# design.net
KiCad netlist of a schematic drawn in Altium Designer
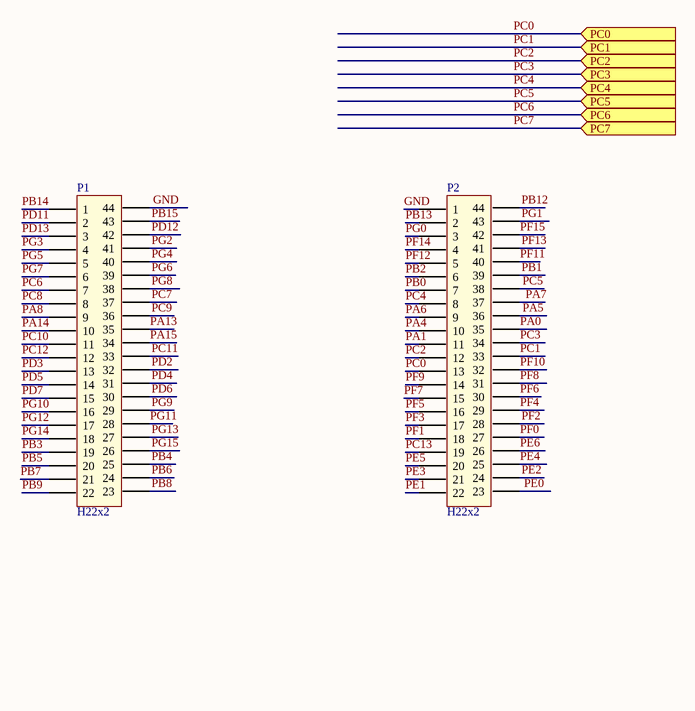
[diagram p0: 接口.SchDoc]

(export (version "E")
  (design (tool "Eeschema 10.0.6"))
  (components
    (comp (ref "P1") (value "H22x2") (footprint "HDR2.54-F-44P") (libsource (lib "Sean") (part "H22x2")))
    (comp (ref "P2") (value "H22x2") (footprint "HDR2.54-F-44P") (libsource (lib "Sean") (part "H22x2")))
  )
  (nets
    (net (code "1") (name "/GND") (class "Default")
      (node (ref "P1") (pin "44") (pinfunction "44_44") (pintype "passive"))
      (node (ref "P2") (pin "1") (pinfunction "1_1") (pintype "passive"))
    )
    (net (code "2") (name "/PA0") (class "Default")
      (node (ref "P2") (pin "35") (pinfunction "35_35") (pintype "passive"))
    )
    (net (code "3") (name "/PA1") (class "Default")
      (node (ref "P2") (pin "11") (pinfunction "11_11") (pintype "passive"))
    )
    (net (code "4") (name "/PA4") (class "Default")
      (node (ref "P2") (pin "10") (pinfunction "10_10") (pintype "passive"))
    )
    (net (code "5") (name "/PA5") (class "Default")
      (node (ref "P2") (pin "36") (pinfunction "36_36") (pintype "passive"))
    )
    (net (code "6") (name "/PA6") (class "Default")
      (node (ref "P2") (pin "9") (pinfunction "9_9") (pintype "passive"))
    )
    (net (code "7") (name "/PA7") (class "Default")
      (node (ref "P2") (pin "37") (pinfunction "37_37") (pintype "passive"))
    )
    (net (code "8") (name "/PA8") (class "Default")
      (node (ref "P1") (pin "9") (pinfunction "9_9") (pintype "passive"))
    )
    (net (code "9") (name "/PA13") (class "Default")
      (node (ref "P1") (pin "35") (pinfunction "35_35") (pintype "passive"))
    )
    (net (code "10") (name "/PA14") (class "Default")
      (node (ref "P1") (pin "10") (pinfunction "10_10") (pintype "passive"))
    )
    (net (code "11") (name "/PA15") (class "Default")
      (node (ref "P1") (pin "34") (pinfunction "34_34") (pintype "passive"))
    )
    (net (code "12") (name "/PB0") (class "Default")
      (node (ref "P2") (pin "7") (pinfunction "7_7") (pintype "passive"))
    )
    (net (code "13") (name "/PB1") (class "Default")
      (node (ref "P2") (pin "39") (pinfunction "39_39") (pintype "passive"))
    )
    (net (code "14") (name "/PB2") (class "Default")
      (node (ref "P2") (pin "6") (pinfunction "6_6") (pintype "passive"))
    )
    (net (code "15") (name "/PB3") (class "Default")
      (node (ref "P1") (pin "19") (pinfunction "19_19") (pintype "passive"))
    )
    (net (code "16") (name "/PB4") (class "Default")
      (node (ref "P1") (pin "25") (pinfunction "25_25") (pintype "passive"))
    )
    (net (code "17") (name "/PB5") (class "Default")
      (node (ref "P1") (pin "20") (pinfunction "20_20") (pintype "passive"))
    )
    (net (code "18") (name "/PB6") (class "Default")
      (node (ref "P1") (pin "24") (pinfunction "24_24") (pintype "passive"))
    )
    (net (code "19") (name "/PB7") (class "Default")
      (node (ref "P1") (pin "21") (pinfunction "21_21") (pintype "passive"))
    )
    (net (code "20") (name "/PB8") (class "Default")
      (node (ref "P1") (pin "23") (pinfunction "23_23") (pintype "passive"))
    )
    (net (code "21") (name "/PB9") (class "Default")
      (node (ref "P1") (pin "22") (pinfunction "22_22") (pintype "passive"))
    )
    (net (code "22") (name "/PB12") (class "Default")
      (node (ref "P2") (pin "44") (pinfunction "44_44") (pintype "passive"))
    )
    (net (code "23") (name "/PB13") (class "Default")
      (node (ref "P2") (pin "2") (pinfunction "2_2") (pintype "passive"))
    )
    (net (code "24") (name "/PB14") (class "Default")
      (node (ref "P1") (pin "1") (pinfunction "1_1") (pintype "passive"))
    )
    (net (code "25") (name "/PB15") (class "Default")
      (node (ref "P1") (pin "43") (pinfunction "43_43") (pintype "passive"))
    )
    (net (code "26") (name "/PC0") (class "Default")
      (node (ref "P2") (pin "13") (pinfunction "13_13") (pintype "passive"))
    )
    (net (code "27") (name "/PC1") (class "Default")
      (node (ref "P2") (pin "33") (pinfunction "33_33") (pintype "passive"))
    )
    (net (code "28") (name "/PC2") (class "Default")
      (node (ref "P2") (pin "12") (pinfunction "12_12") (pintype "passive"))
    )
    (net (code "29") (name "/PC3") (class "Default")
      (node (ref "P2") (pin "34") (pinfunction "34_34") (pintype "passive"))
    )
    (net (code "30") (name "/PC4") (class "Default")
      (node (ref "P2") (pin "8") (pinfunction "8_8") (pintype "passive"))
    )
    (net (code "31") (name "/PC5") (class "Default")
      (node (ref "P2") (pin "38") (pinfunction "38_38") (pintype "passive"))
    )
    (net (code "32") (name "/PC6") (class "Default")
      (node (ref "P1") (pin "7") (pinfunction "7_7") (pintype "passive"))
    )
    (net (code "33") (name "/PC7") (class "Default")
      (node (ref "P1") (pin "37") (pinfunction "37_37") (pintype "passive"))
    )
    (net (code "34") (name "/PC8") (class "Default")
      (node (ref "P1") (pin "8") (pinfunction "8_8") (pintype "passive"))
    )
    (net (code "35") (name "/PC9") (class "Default")
      (node (ref "P1") (pin "36") (pinfunction "36_36") (pintype "passive"))
    )
    (net (code "36") (name "/PC10") (class "Default")
      (node (ref "P1") (pin "11") (pinfunction "11_11") (pintype "passive"))
    )
    (net (code "37") (name "/PC11") (class "Default")
      (node (ref "P1") (pin "33") (pinfunction "33_33") (pintype "passive"))
    )
    (net (code "38") (name "/PC12") (class "Default")
      (node (ref "P1") (pin "12") (pinfunction "12_12") (pintype "passive"))
    )
    (net (code "39") (name "/PC13") (class "Default")
      (node (ref "P2") (pin "19") (pinfunction "19_19") (pintype "passive"))
    )
    (net (code "40") (name "/PD2") (class "Default")
      (node (ref "P1") (pin "32") (pinfunction "32_32") (pintype "passive"))
    )
    (net (code "41") (name "/PD3") (class "Default")
      (node (ref "P1") (pin "13") (pinfunction "13_13") (pintype "passive"))
    )
    (net (code "42") (name "/PD4") (class "Default")
      (node (ref "P1") (pin "31") (pinfunction "31_31") (pintype "passive"))
    )
    (net (code "43") (name "/PD5") (class "Default")
      (node (ref "P1") (pin "14") (pinfunction "14_14") (pintype "passive"))
    )
    (net (code "44") (name "/PD6") (class "Default")
      (node (ref "P1") (pin "30") (pinfunction "30_30") (pintype "passive"))
    )
    (net (code "45") (name "/PD7") (class "Default")
      (node (ref "P1") (pin "15") (pinfunction "15_15") (pintype "passive"))
    )
    (net (code "46") (name "/PD11") (class "Default")
      (node (ref "P1") (pin "2") (pinfunction "2_2") (pintype "passive"))
    )
    (net (code "47") (name "/PD12") (class "Default")
      (node (ref "P1") (pin "42") (pinfunction "42_42") (pintype "passive"))
    )
    (net (code "48") (name "/PD13") (class "Default")
      (node (ref "P1") (pin "3") (pinfunction "3_3") (pintype "passive"))
    )
    (net (code "49") (name "/PE0") (class "Default")
      (node (ref "P2") (pin "23") (pinfunction "23_23") (pintype "passive"))
    )
    (net (code "50") (name "/PE1") (class "Default")
      (node (ref "P2") (pin "22") (pinfunction "22_22") (pintype "passive"))
    )
    (net (code "51") (name "/PE2") (class "Default")
      (node (ref "P2") (pin "24") (pinfunction "24_24") (pintype "passive"))
    )
    (net (code "52") (name "/PE3") (class "Default")
      (node (ref "P2") (pin "21") (pinfunction "21_21") (pintype "passive"))
    )
    (net (code "53") (name "/PE4") (class "Default")
      (node (ref "P2") (pin "25") (pinfunction "25_25") (pintype "passive"))
    )
    (net (code "54") (name "/PE5") (class "Default")
      (node (ref "P2") (pin "20") (pinfunction "20_20") (pintype "passive"))
    )
    (net (code "55") (name "/PE6") (class "Default")
      (node (ref "P2") (pin "26") (pinfunction "26_26") (pintype "passive"))
    )
    (net (code "56") (name "/PF0") (class "Default")
      (node (ref "P2") (pin "27") (pinfunction "27_27") (pintype "passive"))
    )
    (net (code "57") (name "/PF1") (class "Default")
      (node (ref "P2") (pin "18") (pinfunction "18_18") (pintype "passive"))
    )
    (net (code "58") (name "/PF2") (class "Default")
      (node (ref "P2") (pin "28") (pinfunction "28_28") (pintype "passive"))
    )
    (net (code "59") (name "/PF3") (class "Default")
      (node (ref "P2") (pin "17") (pinfunction "17_17") (pintype "passive"))
    )
    (net (code "60") (name "/PF4") (class "Default")
      (node (ref "P2") (pin "29") (pinfunction "29_29") (pintype "passive"))
    )
    (net (code "61") (name "/PF5") (class "Default")
      (node (ref "P2") (pin "16") (pinfunction "16_16") (pintype "passive"))
    )
    (net (code "62") (name "/PF6") (class "Default")
      (node (ref "P2") (pin "30") (pinfunction "30_30") (pintype "passive"))
    )
    (net (code "63") (name "/PF7") (class "Default")
      (node (ref "P2") (pin "15") (pinfunction "15_15") (pintype "passive"))
    )
    (net (code "64") (name "/PF8") (class "Default")
      (node (ref "P2") (pin "31") (pinfunction "31_31") (pintype "passive"))
    )
    (net (code "65") (name "/PF9") (class "Default")
      (node (ref "P2") (pin "14") (pinfunction "14_14") (pintype "passive"))
    )
    (net (code "66") (name "/PF10") (class "Default")
      (node (ref "P2") (pin "32") (pinfunction "32_32") (pintype "passive"))
    )
    (net (code "67") (name "/PF11") (class "Default")
      (node (ref "P2") (pin "40") (pinfunction "40_40") (pintype "passive"))
    )
    (net (code "68") (name "/PF12") (class "Default")
      (node (ref "P2") (pin "5") (pinfunction "5_5") (pintype "passive"))
    )
    (net (code "69") (name "/PF13") (class "Default")
      (node (ref "P2") (pin "41") (pinfunction "41_41") (pintype "passive"))
    )
    (net (code "70") (name "/PF14") (class "Default")
      (node (ref "P2") (pin "4") (pinfunction "4_4") (pintype "passive"))
    )
    (net (code "71") (name "/PF15") (class "Default")
      (node (ref "P2") (pin "42") (pinfunction "42_42") (pintype "passive"))
    )
    (net (code "72") (name "/PG0") (class "Default")
      (node (ref "P2") (pin "3") (pinfunction "3_3") (pintype "passive"))
    )
    (net (code "73") (name "/PG1") (class "Default")
      (node (ref "P2") (pin "43") (pinfunction "43_43") (pintype "passive"))
    )
    (net (code "74") (name "/PG2") (class "Default")
      (node (ref "P1") (pin "41") (pinfunction "41_41") (pintype "passive"))
    )
    (net (code "75") (name "/PG3") (class "Default")
      (node (ref "P1") (pin "4") (pinfunction "4_4") (pintype "passive"))
    )
    (net (code "76") (name "/PG4") (class "Default")
      (node (ref "P1") (pin "40") (pinfunction "40_40") (pintype "passive"))
    )
    (net (code "77") (name "/PG5") (class "Default")
      (node (ref "P1") (pin "5") (pinfunction "5_5") (pintype "passive"))
    )
    (net (code "78") (name "/PG6") (class "Default")
      (node (ref "P1") (pin "39") (pinfunction "39_39") (pintype "passive"))
    )
    (net (code "79") (name "/PG7") (class "Default")
      (node (ref "P1") (pin "6") (pinfunction "6_6") (pintype "passive"))
    )
    (net (code "80") (name "/PG8") (class "Default")
      (node (ref "P1") (pin "38") (pinfunction "38_38") (pintype "passive"))
    )
    (net (code "81") (name "/PG9") (class "Default")
      (node (ref "P1") (pin "29") (pinfunction "29_29") (pintype "passive"))
    )
    (net (code "82") (name "/PG10") (class "Default")
      (node (ref "P1") (pin "16") (pinfunction "16_16") (pintype "passive"))
    )
    (net (code "83") (name "/PG11") (class "Default")
      (node (ref "P1") (pin "28") (pinfunction "28_28") (pintype "passive"))
    )
    (net (code "84") (name "/PG12") (class "Default")
      (node (ref "P1") (pin "17") (pinfunction "17_17") (pintype "passive"))
    )
    (net (code "85") (name "/PG13") (class "Default")
      (node (ref "P1") (pin "27") (pinfunction "27_27") (pintype "passive"))
    )
    (net (code "86") (name "/PG14") (class "Default")
      (node (ref "P1") (pin "18") (pinfunction "18_18") (pintype "passive"))
    )
    (net (code "87") (name "/PG15") (class "Default")
      (node (ref "P1") (pin "26") (pinfunction "26_26") (pintype "passive"))
    )
  )
)
